# USB.net
KiCad netlist of a schematic drawn in Altium Designer
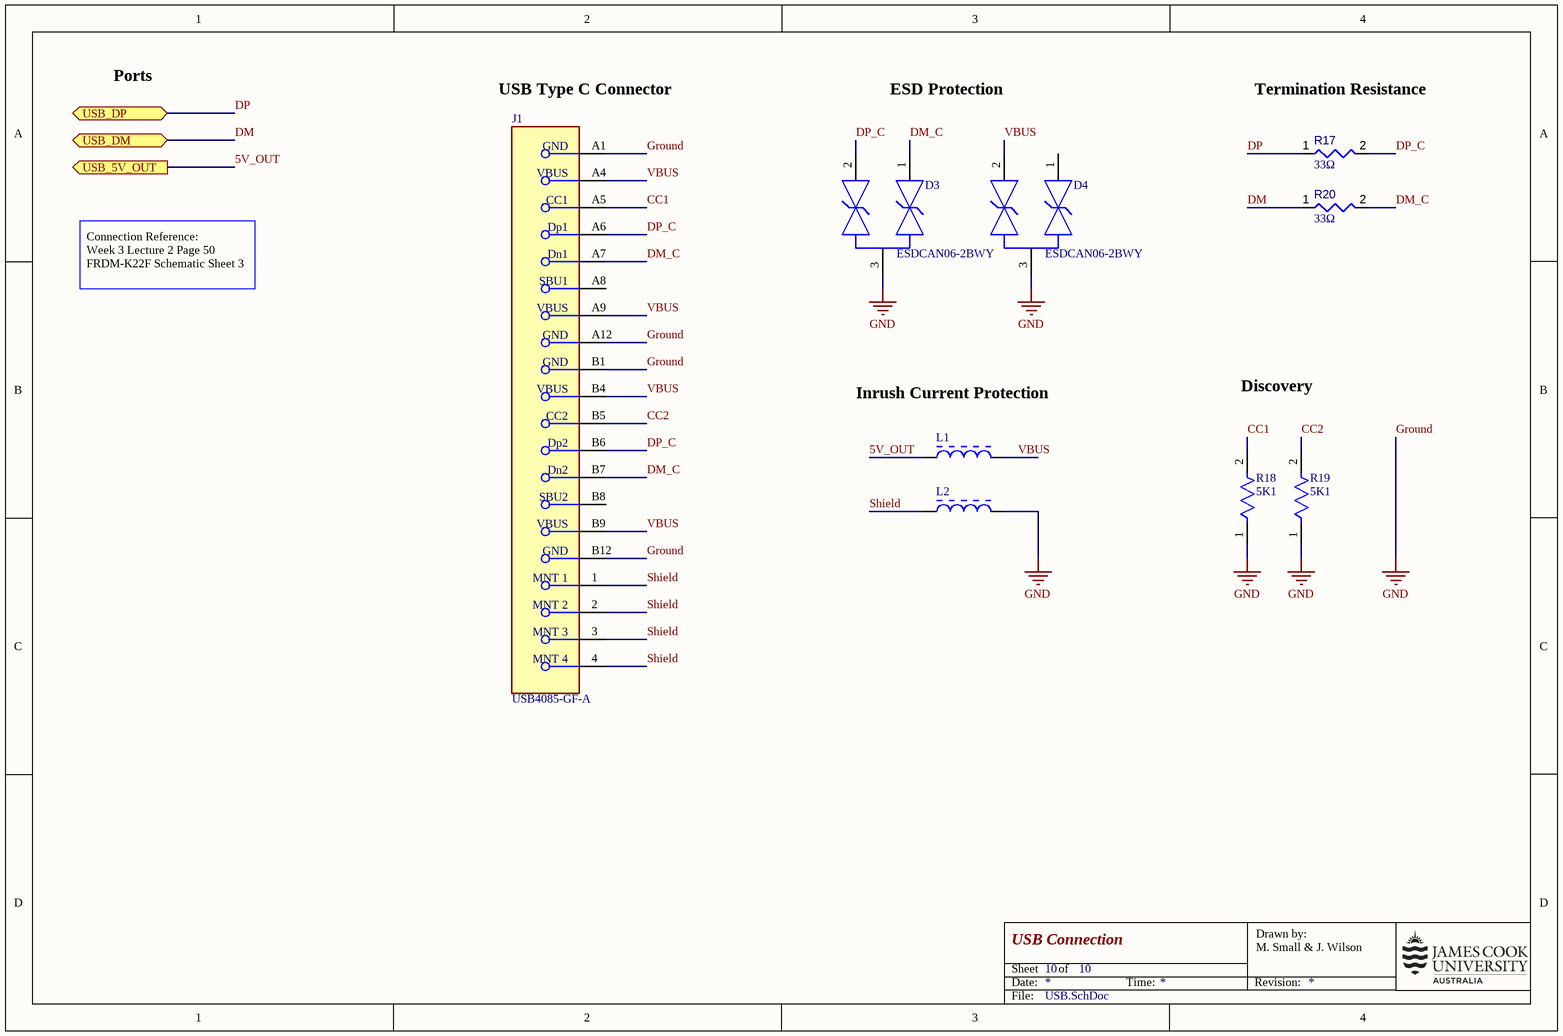
[diagram p0: USB.SchDoc]

(export (version "E")
  (design (tool "Eeschema 10.0.6"))
  (components
    (comp (ref "D3")
      (value "ESDCAN06-2BWY")
      (footprint "FP-SOT323-3L-MFG")
      (description "TVS DIODE 35V 59V SOT323-3")
      (fields
        (field (name "MANUFACTURER") "STMicroelectronics")
        (field (name "OCTOPART") "https://octopart.com/esdcan02-2bwy-stmicroelectronics-58631133")
      )
      (libsource (lib "Altium Content Vault") (part "0b9019fb5e52ed66df21ec1535be59d"))
    )
    (comp (ref "D4")
      (value "ESDCAN06-2BWY")
      (footprint "FP-SOT323-3L-MFG")
      (description "TVS DIODE 35V 59V SOT323-3")
      (fields
        (field (name "MANUFACTURER") "STMicroelectronics")
        (field (name "OCTOPART") "https://octopart.com/esdcan02-2bwy-stmicroelectronics-58631133")
      )
      (libsource (lib "Altium Content Vault") (part "0b9019fb5e52ed66df21ec1535be59d"))
    )
    (comp (ref "J1")
      (value "USB4085-GF-A")
      (footprint "FP-USB4085-GF-A-MFG")
      (description "CONN RCPT USB2.0 TYPEC 16POS")
      (fields
        (field (name "MANUFACTURER") "Global Connector Technology")
        (field (name "OCTOPART") "https://octopart.com/usb4085-gf-a-global+connector+technology-94773699")
      )
      (libsource (lib "Altium Content Vault") (part "f6997dba88850a18107ac0013977506"))
    )
    (comp (ref "L1")
      (value "Z0805C331BPWZT")
      (footprint "INDC2013X105X50ML20T20")
      (fields (field (name "MANUFACTURER") "KEMET") (field (name "TOLERANCE") "25%"))
      (libsource (lib "James Cook University") (part "IND-FB-2"))
    )
    (comp (ref "L2")
      (value "Z0805C331BPWZT")
      (footprint "INDC2013X105X50ML20T20")
      (fields (field (name "MANUFACTURER") "KEMET") (field (name "TOLERANCE") "25%"))
      (libsource (lib "James Cook University") (part "IND-FB-2"))
    )
    (comp (ref "R17")
      (value "33Ω")
      (footprint "RESC0805(2012)_L")
      (description "33R 0.125W 5% 0805 (2012 Metric)  SMD")
      (fields (field (name "TOLERANCE") "5%") (field (name "POWER") "0.125W"))
      (libsource (lib "James Cook University") (part "4D7R5J"))
    )
    (comp (ref "R18")
      (value "5K1")
      (footprint "FP-CRCW0805-e3-MFG")
      (description "RES Thick Film, 5K1Ω, 1%, 0.125W, 100ppm/°C, 0805")
      (fields (field (name "TOLERANCE") "1%"))
      (libsource (lib "Altium Content Vault") (part "1029c3af85768c4190bb7ad29bc67b5"))
    )
    (comp (ref "R19")
      (value "5K1")
      (footprint "FP-CRCW0805-e3-MFG")
      (description "RES Thick Film, 5K1Ω, 1%, 0.125W, 100ppm/°C, 0805")
      (fields (field (name "TOLERANCE") "1%"))
      (libsource (lib "Altium Content Vault") (part "1029c3af85768c4190bb7ad29bc67b5"))
    )
    (comp (ref "R20")
      (value "33Ω")
      (footprint "RESC0805(2012)_L")
      (description "33R 0.125W 5% 0805 (2012 Metric)  SMD")
      (fields (field (name "TOLERANCE") "5%") (field (name "POWER") "0.125W"))
      (libsource (lib "James Cook University") (part "4D7R5J"))
    )
  )
  (nets
    (net (code "1") (name "/5V_OUT") (class "Default")
      (node (ref "L1") (pin "1") (pinfunction "1_1") (pintype "passive"))
    )
    (net (code "2") (name "/CC1") (class "Default")
      (node (ref "J1") (pin "A5") (pinfunction "CC1_A5") (pintype "passive"))
      (node (ref "R18") (pin "2") (pinfunction "2_2") (pintype "passive"))
    )
    (net (code "3") (name "/CC2") (class "Default")
      (node (ref "J1") (pin "B5") (pinfunction "CC2_B5") (pintype "passive"))
      (node (ref "R19") (pin "2") (pinfunction "2_2") (pintype "passive"))
    )
    (net (code "4") (name "/DM") (class "Default")
      (node (ref "R20") (pin "1") (pinfunction "1_1") (pintype "passive"))
    )
    (net (code "5") (name "/DM_C") (class "Default")
      (node (ref "D3") (pin "1") (pinfunction "1_1") (pintype "passive"))
      (node (ref "J1") (pin "A7") (pinfunction "Dn1_A7") (pintype "passive"))
      (node (ref "J1") (pin "B7") (pinfunction "Dn2_B7") (pintype "passive"))
      (node (ref "R20") (pin "2") (pinfunction "2_2") (pintype "passive"))
    )
    (net (code "6") (name "/DP") (class "Default")
      (node (ref "R17") (pin "1") (pinfunction "1_1") (pintype "passive"))
    )
    (net (code "7") (name "/DP_C") (class "Default")
      (node (ref "D3") (pin "2") (pinfunction "2_2") (pintype "passive"))
      (node (ref "J1") (pin "A6") (pinfunction "Dp1_A6") (pintype "passive"))
      (node (ref "J1") (pin "B6") (pinfunction "Dp2_B6") (pintype "passive"))
      (node (ref "R17") (pin "2") (pinfunction "2_2") (pintype "passive"))
    )
    (net (code "8") (name "/Shield") (class "Default")
      (node (ref "J1") (pin "1") (pinfunction "MNT_1_1") (pintype "passive"))
      (node (ref "J1") (pin "2") (pinfunction "MNT_2_2") (pintype "passive"))
      (node (ref "J1") (pin "3") (pinfunction "MNT_3_3") (pintype "passive"))
      (node (ref "J1") (pin "4") (pinfunction "MNT_4_4") (pintype "passive"))
      (node (ref "L2") (pin "1") (pinfunction "1_1") (pintype "passive"))
    )
    (net (code "9") (name "/VBUS") (class "Default")
      (node (ref "D4") (pin "2") (pinfunction "2_2") (pintype "passive"))
      (node (ref "J1") (pin "A4") (pinfunction "VBUS_A4") (pintype "power_in"))
      (node (ref "J1") (pin "A9") (pinfunction "VBUS_A9") (pintype "power_in"))
      (node (ref "J1") (pin "B4") (pinfunction "VBUS_B4") (pintype "power_in"))
      (node (ref "J1") (pin "B9") (pinfunction "VBUS_B9") (pintype "power_in"))
      (node (ref "L1") (pin "2") (pinfunction "2_2") (pintype "passive"))
    )
    (net (code "10") (name "GND") (class "Default")
      (node (ref "D3") (pin "3") (pinfunction "3_3") (pintype "passive"))
      (node (ref "D4") (pin "3") (pinfunction "3_3") (pintype "passive"))
      (node (ref "J1") (pin "A1") (pinfunction "GND_A1") (pintype "power_in"))
      (node (ref "J1") (pin "A12") (pinfunction "GND_A12") (pintype "power_in"))
      (node (ref "J1") (pin "B1") (pinfunction "GND_B1") (pintype "power_in"))
      (node (ref "J1") (pin "B12") (pinfunction "GND_B12") (pintype "power_in"))
      (node (ref "L2") (pin "2") (pinfunction "2_2") (pintype "passive"))
      (node (ref "R18") (pin "1") (pinfunction "1_1") (pintype "passive"))
      (node (ref "R19") (pin "1") (pinfunction "1_1") (pintype "passive"))
    )
    (net (code "11") (name "unconnected-(D4-Pad1)") (class "Default")
      (node (ref "D4") (pin "1") (pinfunction "1_1") (pintype "passive"))
    )
    (net (code "12") (name "unconnected-(J1-SBU1-PadA8)") (class "Default")
      (node (ref "J1") (pin "A8") (pinfunction "SBU1_A8") (pintype "passive"))
    )
    (net (code "13") (name "unconnected-(J1-SBU2-PadB8)") (class "Default")
      (node (ref "J1") (pin "B8") (pinfunction "SBU2_B8") (pintype "passive"))
    )
  )
)
